# PSPS_AVNC_SRD_sensors-2020-10-23_FABRICA.net
KiCad netlist of a schematic drawn in EAGLE
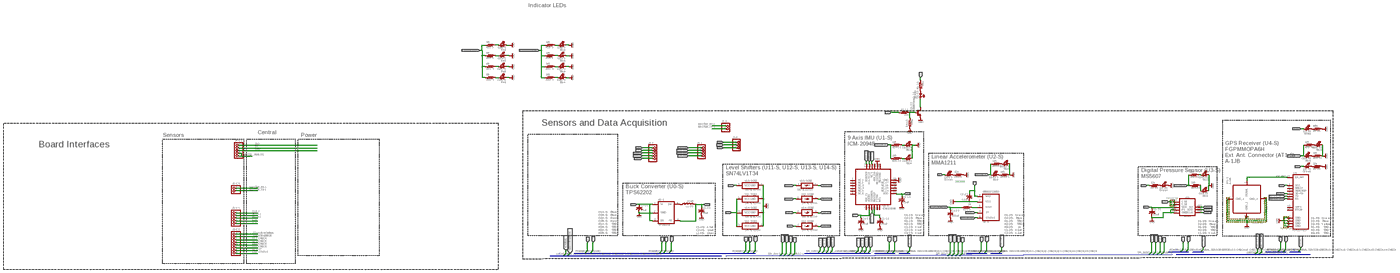
[diagram p0: schematic, sheet 1, overview]
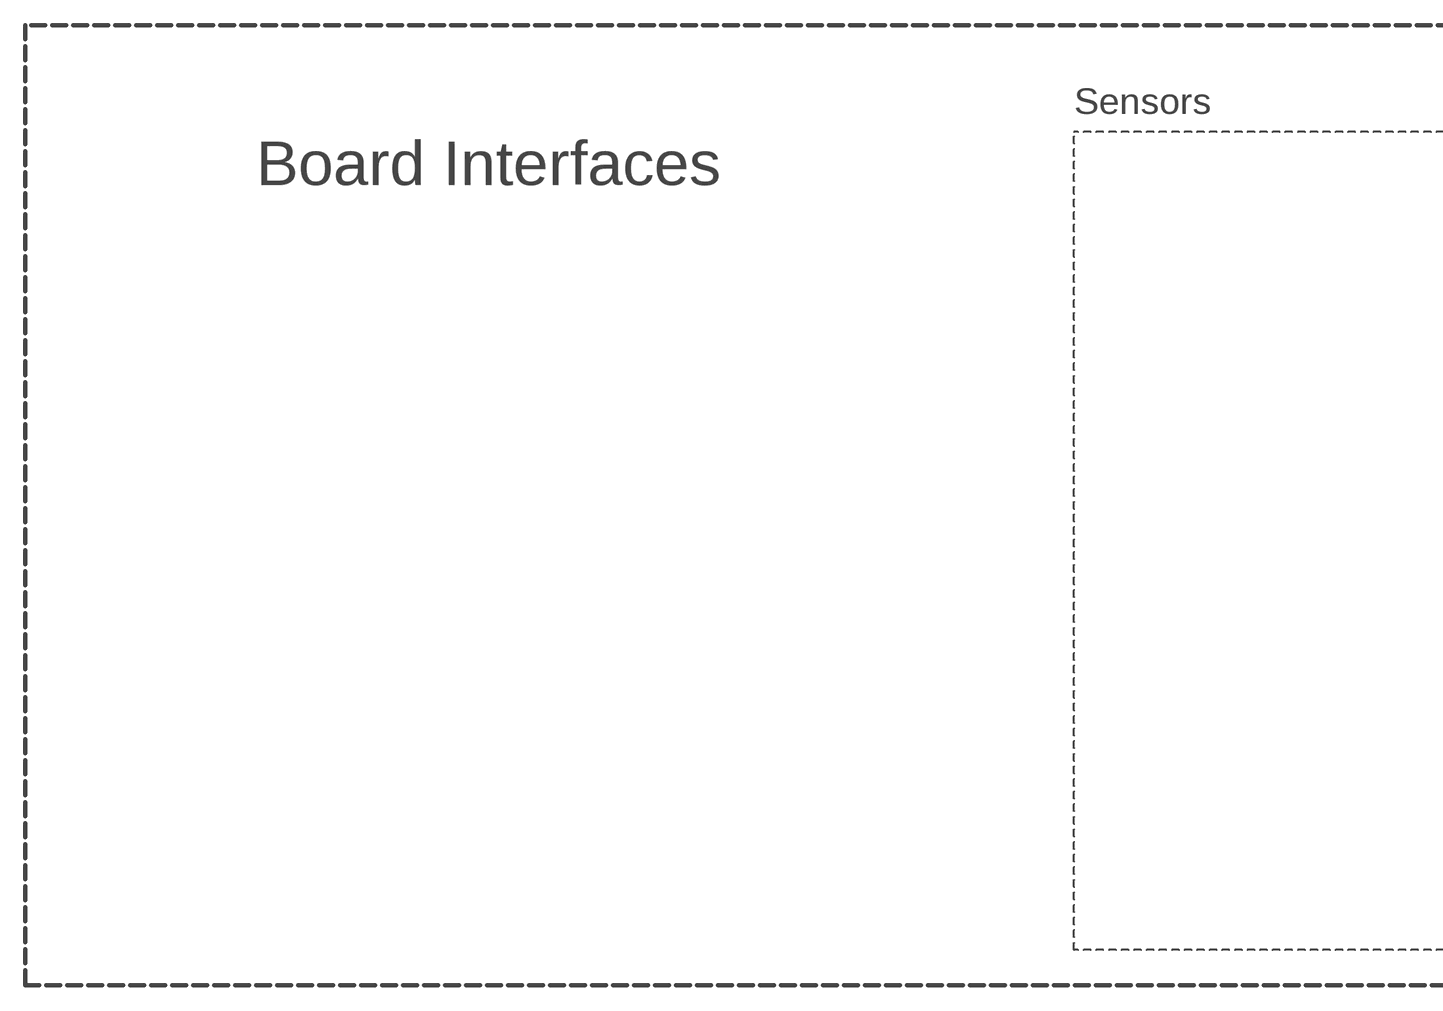
[diagram p1: schematic, sheet 1, part 1 of 4]
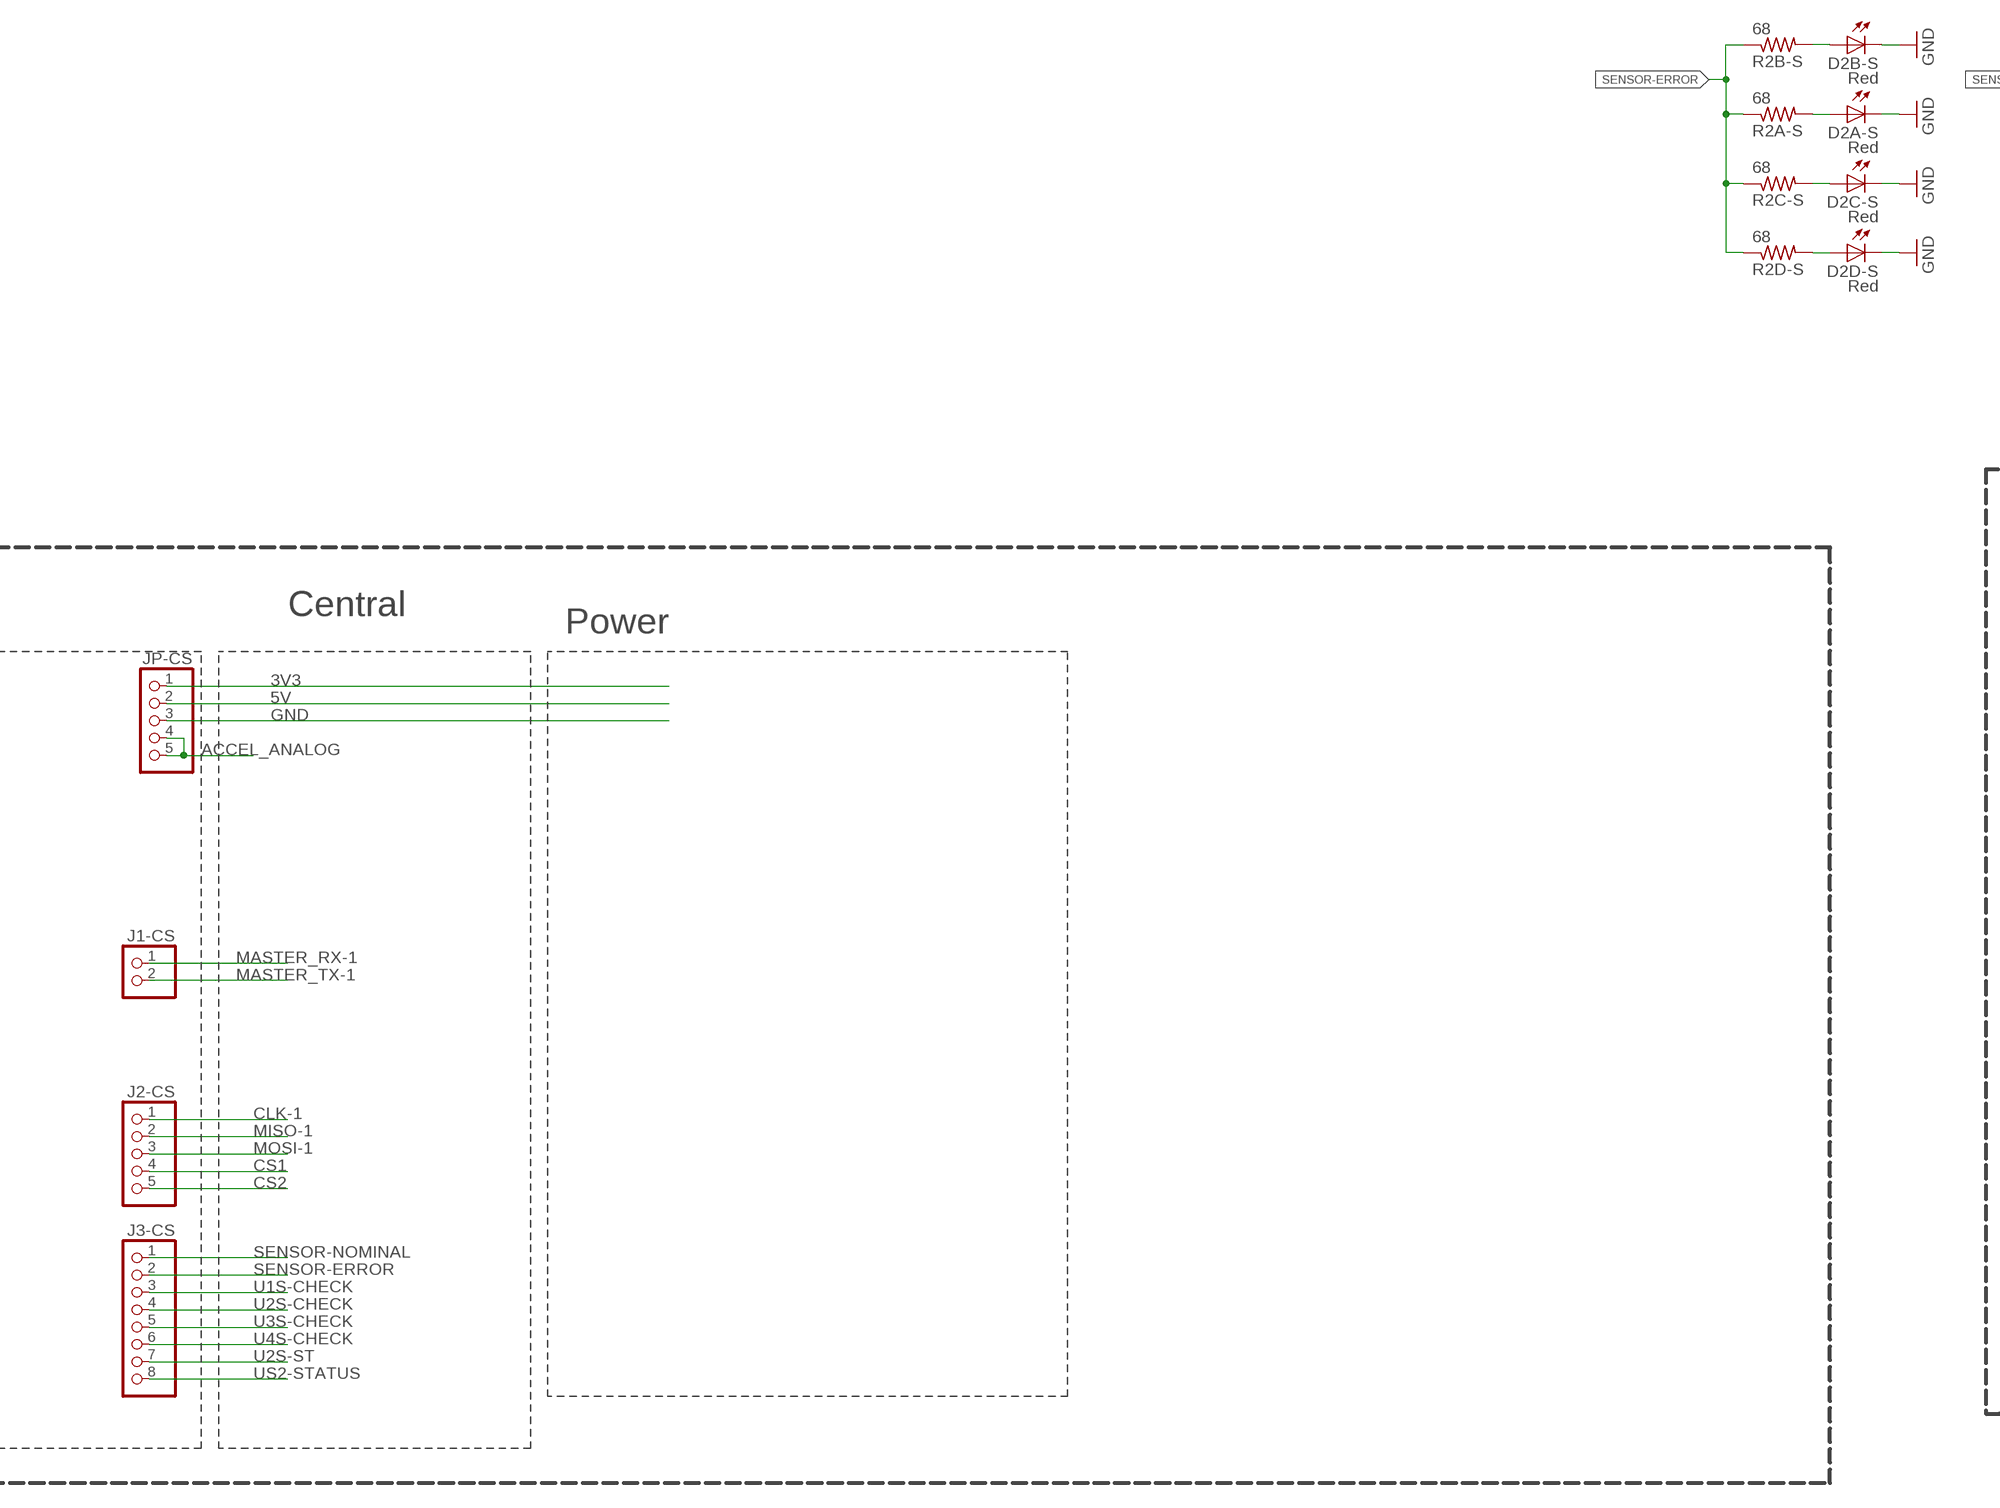
[diagram p2: schematic, sheet 1, part 2 of 4]
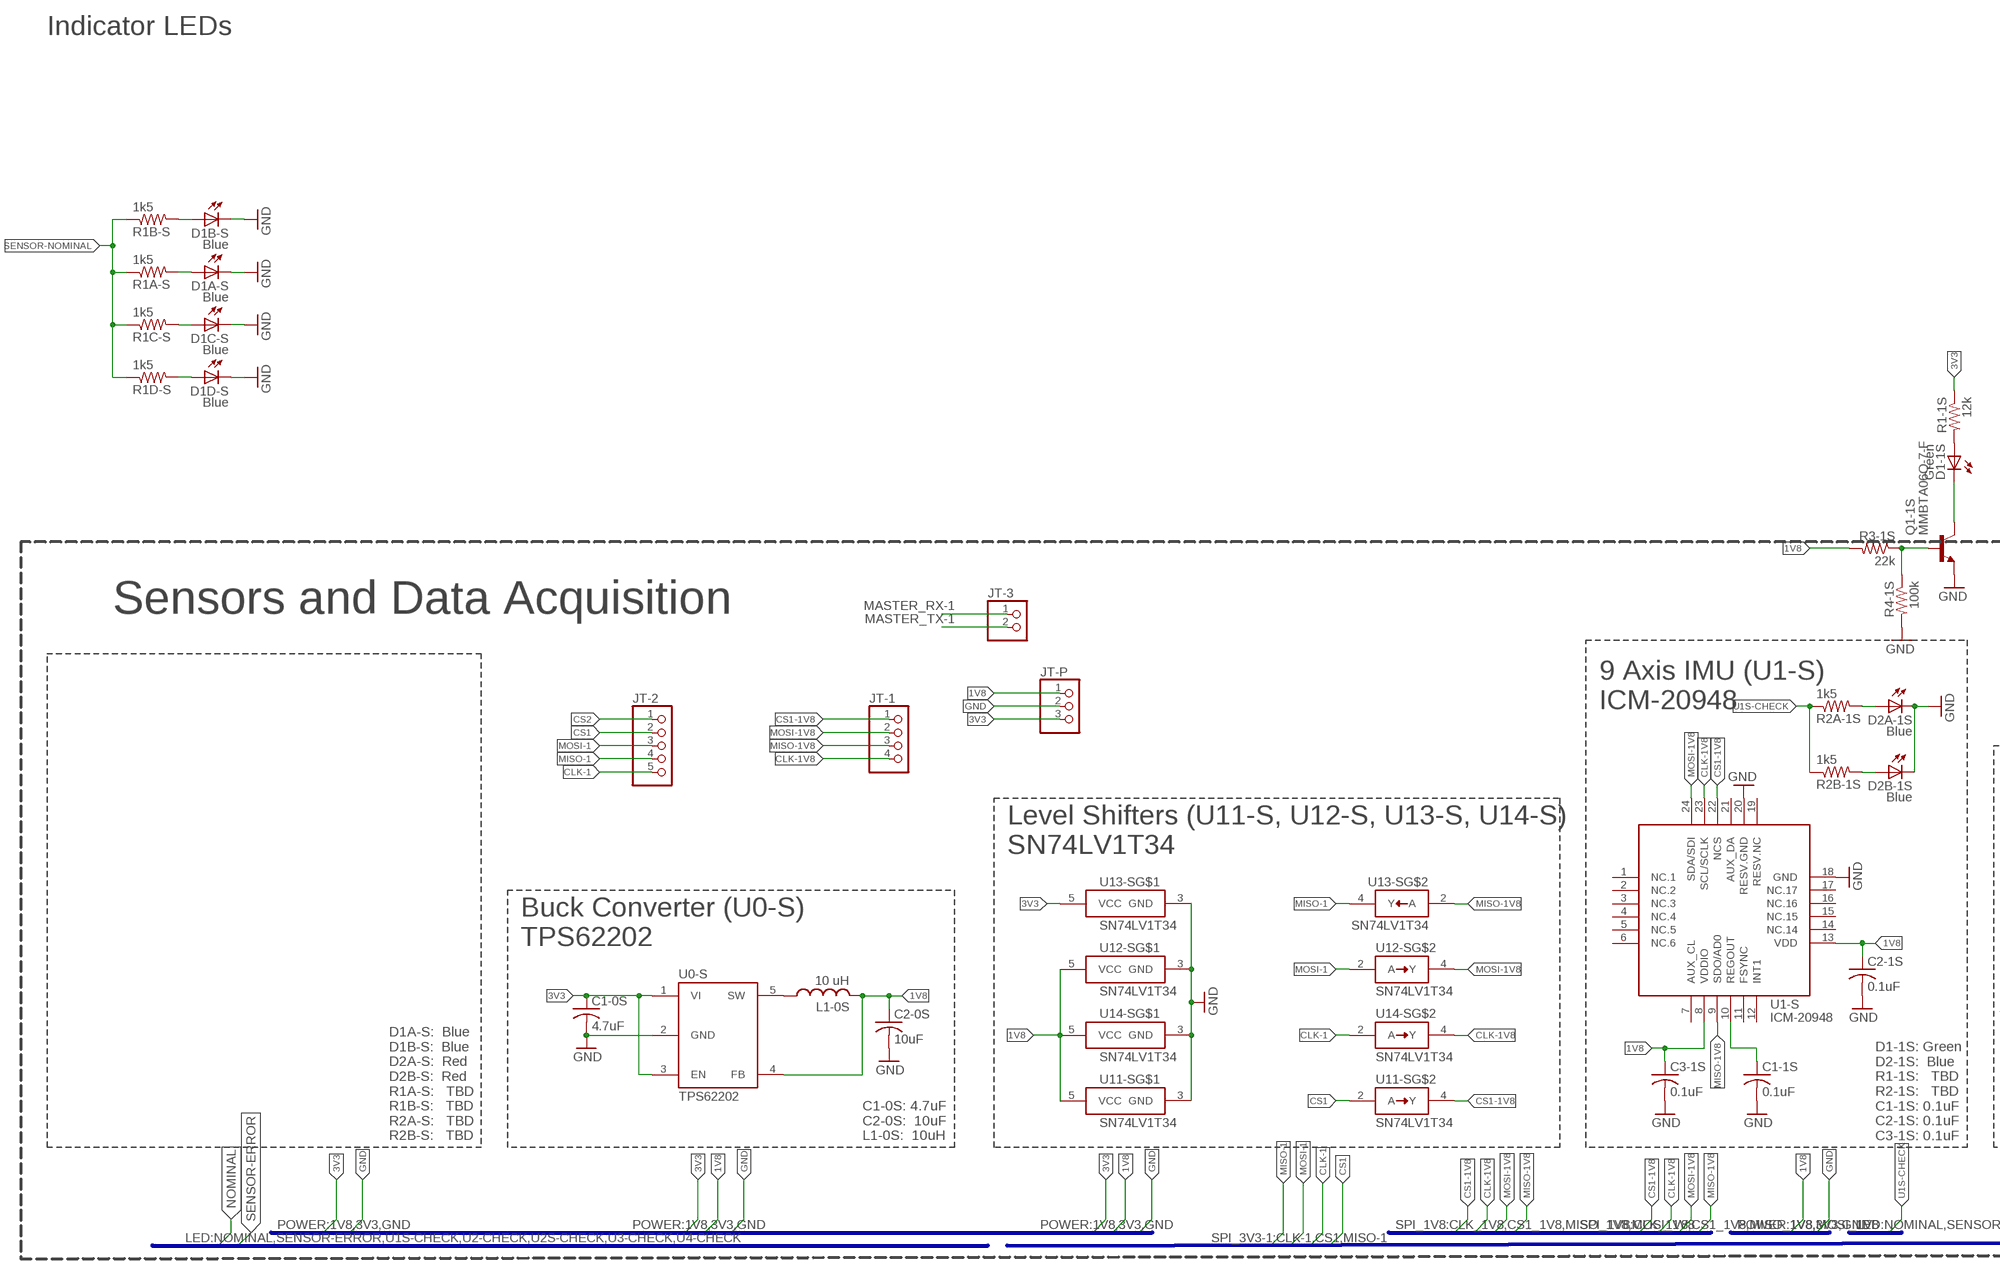
[diagram p3: schematic, sheet 1, part 3 of 4]
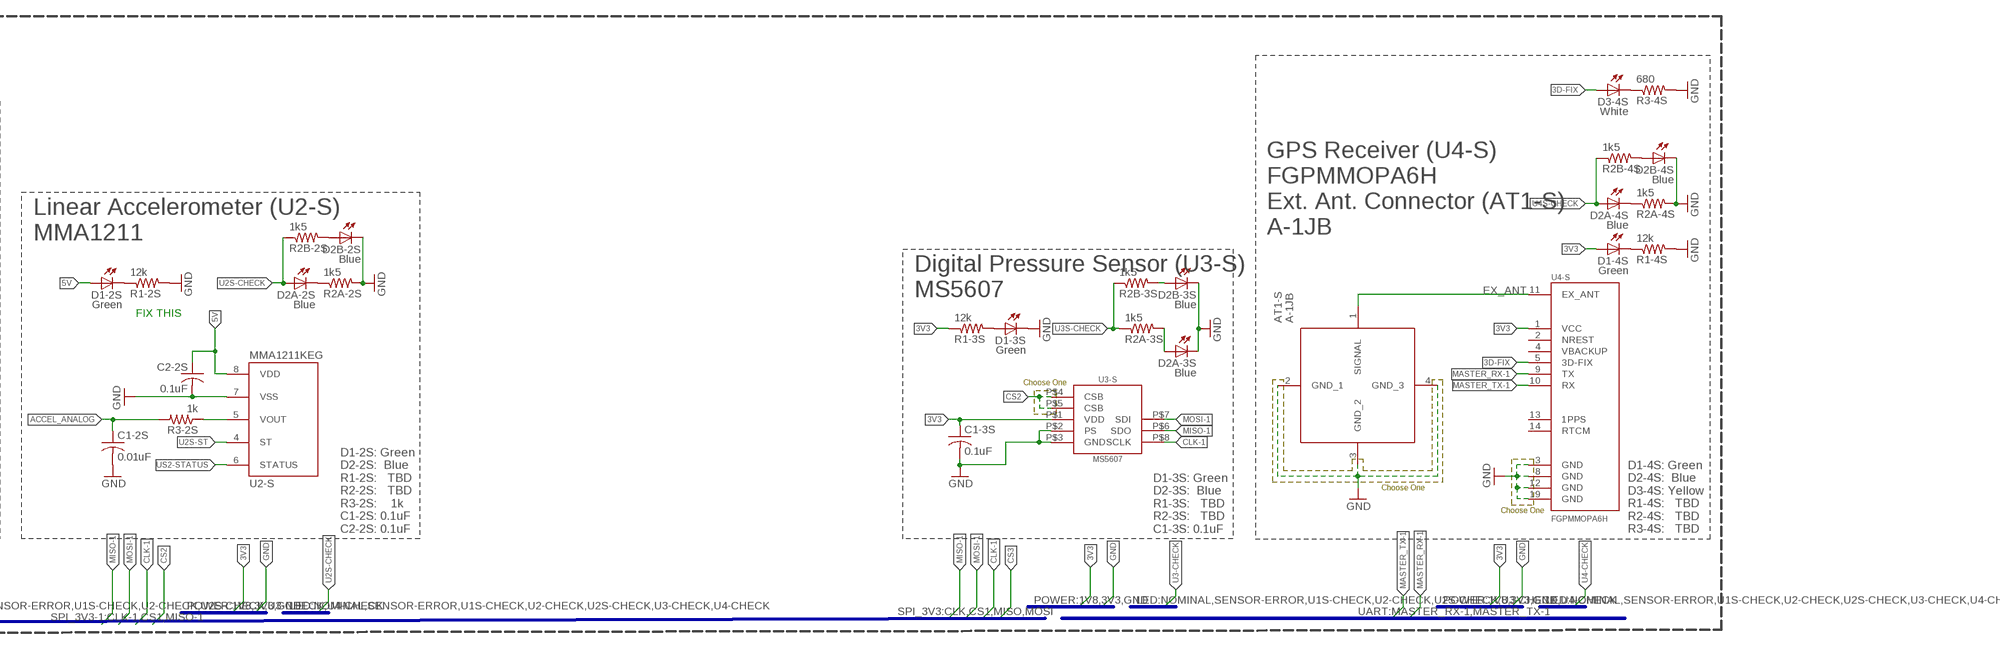
[diagram p4: schematic, sheet 1, part 4 of 4]

(export (version "E")
  (design (tool "Eeschema 10.0.6"))
  (components
    (comp (ref "AT1-S")
      (value "A-1JB")
      (footprint "eagle-import:A1JB")
      (fields (field (name "MOUSER_PART_NUMBER") "523-A-1JB"))
      (libsource (lib "eagle-import") (part "A-1JB"))
    )
    (comp (ref "C1-0S")
      (value "4.7uF")
      (footprint "eagle-import:C0805")
      (libsource (lib "eagle-import") (part "C-USC0805"))
    )
    (comp (ref "C1-1S")
      (value "0.1uF")
      (footprint "eagle-import:C0805")
      (libsource (lib "eagle-import") (part "C-USC0805"))
    )
    (comp (ref "C1-2S")
      (value "0.01uF")
      (footprint "eagle-import:C0805")
      (libsource (lib "eagle-import") (part "C-USC0805"))
    )
    (comp (ref "C1-3S")
      (value "0.1uF")
      (footprint "eagle-import:C0805")
      (libsource (lib "eagle-import") (part "C-USC0805"))
    )
    (comp (ref "C2-0S")
      (value "10uF")
      (footprint "eagle-import:C0805")
      (libsource (lib "eagle-import") (part "C-USC0805"))
    )
    (comp (ref "C2-1S")
      (value "0.1uF")
      (footprint "eagle-import:C0805")
      (libsource (lib "eagle-import") (part "C-USC0805"))
    )
    (comp (ref "C2-2S")
      (value "0.1uF")
      (footprint "eagle-import:C0805")
      (libsource (lib "eagle-import") (part "C-USC0805"))
    )
    (comp (ref "C3-1S")
      (value "0.1uF")
      (footprint "eagle-import:C0805")
      (libsource (lib "eagle-import") (part "C-USC0805"))
    )
    (comp (ref "D1-1S")
      (value "Green")
      (footprint "eagle-import:CHIPLED_0805")
      (libsource (lib "eagle-import") (part "LEDCHIPLED_0805"))
    )
    (comp (ref "D1-2S")
      (value "Green")
      (footprint "eagle-import:CHIPLED_0805")
      (libsource (lib "eagle-import") (part "LEDCHIPLED_0805"))
    )
    (comp (ref "D1-3S")
      (value "Green")
      (footprint "eagle-import:CHIPLED_0805")
      (libsource (lib "eagle-import") (part "LEDCHIPLED_0805"))
    )
    (comp (ref "D1-4S")
      (value "Green")
      (footprint "eagle-import:CHIPLED_0805")
      (libsource (lib "eagle-import") (part "LEDCHIPLED_0805"))
    )
    (comp (ref "D1A-S")
      (value "Blue")
      (footprint "eagle-import:CHIPLED_0805")
      (libsource (lib "eagle-import") (part "LEDCHIPLED_0805"))
    )
    (comp (ref "D1B-S")
      (value "Blue")
      (footprint "eagle-import:CHIPLED_0805")
      (libsource (lib "eagle-import") (part "LEDCHIPLED_0805"))
    )
    (comp (ref "D1C-S")
      (value "Blue")
      (footprint "eagle-import:CHIPLED_0805")
      (libsource (lib "eagle-import") (part "LEDCHIPLED_0805"))
    )
    (comp (ref "D1D-S")
      (value "Blue")
      (footprint "eagle-import:CHIPLED_0805")
      (libsource (lib "eagle-import") (part "LEDCHIPLED_0805"))
    )
    (comp (ref "D2A-1S")
      (value "Blue")
      (footprint "eagle-import:CHIPLED_0805")
      (libsource (lib "eagle-import") (part "LEDCHIPLED_0805"))
    )
    (comp (ref "D2A-2S")
      (value "Blue")
      (footprint "eagle-import:CHIPLED_0805")
      (libsource (lib "eagle-import") (part "LEDCHIPLED_0805"))
    )
    (comp (ref "D2A-3S")
      (value "Blue")
      (footprint "eagle-import:CHIPLED_0805")
      (libsource (lib "eagle-import") (part "LEDCHIPLED_0805"))
    )
    (comp (ref "D2A-4S")
      (value "Blue")
      (footprint "eagle-import:CHIPLED_0805")
      (libsource (lib "eagle-import") (part "LEDCHIPLED_0805"))
    )
    (comp (ref "D2A-S")
      (value "Red")
      (footprint "eagle-import:CHIPLED_0805")
      (libsource (lib "eagle-import") (part "LEDCHIPLED_0805"))
    )
    (comp (ref "D2B-1S")
      (value "Blue")
      (footprint "eagle-import:CHIPLED_0805")
      (libsource (lib "eagle-import") (part "LEDCHIPLED_0805"))
    )
    (comp (ref "D2B-2S")
      (value "Blue")
      (footprint "eagle-import:CHIPLED_0805")
      (libsource (lib "eagle-import") (part "LEDCHIPLED_0805"))
    )
    (comp (ref "D2B-3S")
      (value "Blue")
      (footprint "eagle-import:CHIPLED_0805")
      (libsource (lib "eagle-import") (part "LEDCHIPLED_0805"))
    )
    (comp (ref "D2B-4S")
      (value "Blue")
      (footprint "eagle-import:CHIPLED_0805")
      (libsource (lib "eagle-import") (part "LEDCHIPLED_0805"))
    )
    (comp (ref "D2B-S")
      (value "Red")
      (footprint "eagle-import:CHIPLED_0805")
      (libsource (lib "eagle-import") (part "LEDCHIPLED_0805"))
    )
    (comp (ref "D2C-S")
      (value "Red")
      (footprint "eagle-import:CHIPLED_0805")
      (libsource (lib "eagle-import") (part "LEDCHIPLED_0805"))
    )
    (comp (ref "D2D-S")
      (value "Red")
      (footprint "eagle-import:CHIPLED_0805")
      (libsource (lib "eagle-import") (part "LEDCHIPLED_0805"))
    )
    (comp (ref "D3-4S")
      (value "White")
      (footprint "eagle-import:CHIPLED_0805")
      (libsource (lib "eagle-import") (part "LEDCHIPLED_0805"))
    )
    (comp (ref "J1-CS")
      (value "PINHD-1X2")
      (footprint "eagle-import:1X02")
      (libsource (lib "eagle-import") (part "PINHD-1X2"))
    )
    (comp (ref "J2-CS")
      (value "PINHD-1X5")
      (footprint "eagle-import:1X05")
      (libsource (lib "eagle-import") (part "PINHD-1X5"))
    )
    (comp (ref "J3-CS")
      (value "PINHD-1X8")
      (footprint "eagle-import:1X08")
      (libsource (lib "eagle-import") (part "PINHD-1X8"))
    )
    (comp (ref "JP-CS")
      (value "PINHD-1X5")
      (footprint "eagle-import:1X05")
      (libsource (lib "eagle-import") (part "PINHD-1X5"))
    )
    (comp (ref "JT-1")
      (value "PINHD-1X4")
      (footprint "eagle-import:1X04")
      (libsource (lib "eagle-import") (part "PINHD-1X4"))
    )
    (comp (ref "JT-2")
      (value "PINHD-1X5")
      (footprint "eagle-import:1X05")
      (libsource (lib "eagle-import") (part "PINHD-1X5"))
    )
    (comp (ref "JT-3")
      (value "PINHD-1X2")
      (footprint "eagle-import:1X02")
      (libsource (lib "eagle-import") (part "PINHD-1X2"))
    )
    (comp (ref "JT-P")
      (value "PINHD-1X3")
      (footprint "eagle-import:1X03")
      (libsource (lib "eagle-import") (part "PINHD-1X3"))
    )
    (comp (ref "L1-0S")
      (value "10 uH")
      (footprint "eagle-import:L1812")
      (libsource (lib "eagle-import") (part "L-USL1812"))
    )
    (comp (ref "Q1-1S")
      (value "MMBTA06Q-7-F")
      (footprint "eagle-import:SOT23")
      (libsource (lib "eagle-import") (part "NPN_TRANSISTOR"))
    )
    (comp (ref "R1-1S")
      (value "12k")
      (footprint "eagle-import:R0805")
      (libsource (lib "eagle-import") (part "R-US_R0805"))
    )
    (comp (ref "R1-2S")
      (value "12k")
      (footprint "eagle-import:R0805")
      (libsource (lib "eagle-import") (part "R-US_R0805"))
    )
    (comp (ref "R1-3S")
      (value "12k")
      (footprint "eagle-import:R0805")
      (libsource (lib "eagle-import") (part "R-US_R0805"))
    )
    (comp (ref "R1-4S")
      (value "12k")
      (footprint "eagle-import:R0805")
      (libsource (lib "eagle-import") (part "R-US_R0805"))
    )
    (comp (ref "R1A-S")
      (value "1k5")
      (footprint "eagle-import:R0805")
      (libsource (lib "eagle-import") (part "R-US_R0805"))
    )
    (comp (ref "R1B-S")
      (value "1k5")
      (footprint "eagle-import:R0805")
      (libsource (lib "eagle-import") (part "R-US_R0805"))
    )
    (comp (ref "R1C-S")
      (value "1k5")
      (footprint "eagle-import:R0805")
      (libsource (lib "eagle-import") (part "R-US_R0805"))
    )
    (comp (ref "R1D-S")
      (value "1k5")
      (footprint "eagle-import:R0805")
      (libsource (lib "eagle-import") (part "R-US_R0805"))
    )
    (comp (ref "R2A-1S")
      (value "1k5")
      (footprint "eagle-import:R0805")
      (libsource (lib "eagle-import") (part "R-US_R0805"))
    )
    (comp (ref "R2A-2S")
      (value "1k5")
      (footprint "eagle-import:R0805")
      (libsource (lib "eagle-import") (part "R-US_R0805"))
    )
    (comp (ref "R2A-3S")
      (value "1k5")
      (footprint "eagle-import:R0805")
      (libsource (lib "eagle-import") (part "R-US_R0805"))
    )
    (comp (ref "R2A-4S")
      (value "1k5")
      (footprint "eagle-import:R0805")
      (libsource (lib "eagle-import") (part "R-US_R0805"))
    )
    (comp (ref "R2A-S")
      (value "68")
      (footprint "eagle-import:R0805")
      (libsource (lib "eagle-import") (part "R-US_R0805"))
    )
    (comp (ref "R2B-1S")
      (value "1k5")
      (footprint "eagle-import:R0805")
      (libsource (lib "eagle-import") (part "R-US_R0805"))
    )
    (comp (ref "R2B-2S")
      (value "1k5")
      (footprint "eagle-import:R0805")
      (libsource (lib "eagle-import") (part "R-US_R0805"))
    )
    (comp (ref "R2B-3S")
      (value "1k5")
      (footprint "eagle-import:R0805")
      (libsource (lib "eagle-import") (part "R-US_R0805"))
    )
    (comp (ref "R2B-4S")
      (value "1k5")
      (footprint "eagle-import:R0805")
      (libsource (lib "eagle-import") (part "R-US_R0805"))
    )
    (comp (ref "R2B-S")
      (value "68")
      (footprint "eagle-import:R0805")
      (libsource (lib "eagle-import") (part "R-US_R0805"))
    )
    (comp (ref "R2C-S")
      (value "68")
      (footprint "eagle-import:R0805")
      (libsource (lib "eagle-import") (part "R-US_R0805"))
    )
    (comp (ref "R2D-S")
      (value "68")
      (footprint "eagle-import:R0805")
      (libsource (lib "eagle-import") (part "R-US_R0805"))
    )
    (comp (ref "R3-1S")
      (value "22k")
      (footprint "eagle-import:R0805")
      (libsource (lib "eagle-import") (part "R-US_R0805"))
    )
    (comp (ref "R3-2S")
      (value "1k")
      (footprint "eagle-import:R0805")
      (libsource (lib "eagle-import") (part "R-US_R0805"))
    )
    (comp (ref "R3-4S")
      (value "680")
      (footprint "eagle-import:R0805")
      (libsource (lib "eagle-import") (part "R-US_R0805"))
    )
    (comp (ref "R4-1S")
      (value "100k")
      (footprint "eagle-import:R0805")
      (libsource (lib "eagle-import") (part "R-US_R0805"))
    )
    (comp (ref "U0-S")
      (value "TPS62202")
      (footprint "eagle-import:SOT95P280X145-5")
      (libsource (lib "eagle-import") (part "TPS62202"))
    )
    (comp (ref "U1-S")
      (value "ICM-20948")
      (footprint "eagle-import:QFN40P300X300X105-25T159X175")
      (libsource (lib "eagle-import") (part "ICM-20948"))
    )
    (comp (ref "U2-S")
      (value "MMA1211KEG")
      (footprint "eagle-import:SOIC127P1041X355-16N")
      (libsource (lib "eagle-import") (part "MMA1211KEG"))
    )
    (comp (ref "U3-S")
      (value "MS5607")
      (footprint "eagle-import:MS5607")
      (libsource (lib "eagle-import") (part "MS5607"))
    )
    (comp (ref "U4-S")
      (value "FGPMMOPA6H")
      (footprint "eagle-import:SOIC127P1800X470-20N")
      (libsource (lib "eagle-import") (part "FGPMMOPA6H"))
    )
    (comp (ref "U11-S")
      (value "SN74LV1T34")
      (footprint "eagle-import:SOT65P210X110-5")
      (libsource (lib "eagle-import") (part "SN74LV1T34"))
    )
    (comp (ref "U12-S")
      (value "SN74LV1T34")
      (footprint "eagle-import:SOT65P210X110-5")
      (libsource (lib "eagle-import") (part "SN74LV1T34"))
    )
    (comp (ref "U13-S")
      (value "SN74LV1T34")
      (footprint "eagle-import:SOT65P210X110-5")
      (libsource (lib "eagle-import") (part "SN74LV1T34"))
    )
    (comp (ref "U14-S")
      (value "SN74LV1T34")
      (footprint "eagle-import:SOT65P210X110-5")
      (libsource (lib "eagle-import") (part "SN74LV1T34"))
    )
  )
  (nets
    (net (code "13") (name "/EX_ANT") (class "Default")
      (node (ref "AT1-S") (pin "1") (pinfunction "SIGNAL_1") (pintype "bidirectional"))
      (node (ref "U4-S") (pin "11") (pinfunction "EX_ANT_11") (pintype "bidirectional"))
    )
    (net (code "20") (name "1V8") (class "Default")
      (node (ref "C2-0S") (pin "1") (pinfunction "1_1") (pintype "passive"))
      (node (ref "C2-1S") (pin "1") (pinfunction "1_1") (pintype "passive"))
      (node (ref "C3-1S") (pin "1") (pinfunction "1_1") (pintype "passive"))
      (node (ref "JT-P") (pin "1") (pinfunction "1_1") (pintype "passive"))
      (node (ref "L1-0S") (pin "2") (pinfunction "2_2") (pintype "passive"))
      (node (ref "R3-1S") (pin "2") (pinfunction "2_2") (pintype "passive"))
      (node (ref "U0-S") (pin "4") (pinfunction "FB_4") (pintype "bidirectional"))
      (node (ref "U1-S") (pin "13") (pinfunction "VDD_13") (pintype "bidirectional"))
      (node (ref "U1-S") (pin "8") (pinfunction "VDDIO_8") (pintype "bidirectional"))
      (node (ref "U11-S") (pin "5") (pinfunction "VCC_5") (pintype "bidirectional"))
      (node (ref "U12-S") (pin "5") (pinfunction "VCC_5") (pintype "bidirectional"))
      (node (ref "U14-S") (pin "5") (pinfunction "VCC_5") (pintype "bidirectional"))
    )
    (net (code "21") (name "3D-FIX") (class "Default")
      (node (ref "D3-4S") (pin "A") (pinfunction "A_A") (pintype "passive"))
      (node (ref "U4-S") (pin "5") (pinfunction "3D-FIX_5") (pintype "bidirectional"))
    )
    (net (code "22") (name "3V3") (class "Default")
      (node (ref "C1-0S") (pin "1") (pinfunction "1_1") (pintype "passive"))
      (node (ref "C1-3S") (pin "1") (pinfunction "1_1") (pintype "passive"))
      (node (ref "D1-4S") (pin "A") (pinfunction "A_A") (pintype "passive"))
      (node (ref "JP-CS") (pin "1") (pinfunction "1_1") (pintype "passive"))
      (node (ref "JT-P") (pin "3") (pinfunction "3_3") (pintype "passive"))
      (node (ref "R1-1S") (pin "1") (pinfunction "1_1") (pintype "passive"))
      (node (ref "R1-3S") (pin "1") (pinfunction "1_1") (pintype "passive"))
      (node (ref "U0-S") (pin "1") (pinfunction "VI_1") (pintype "bidirectional"))
      (node (ref "U0-S") (pin "3") (pinfunction "EN_3") (pintype "bidirectional"))
      (node (ref "U13-S") (pin "5") (pinfunction "VCC_5") (pintype "bidirectional"))
      (node (ref "U3-S") (pin "P$1") (pinfunction "VDD_P$1") (pintype "bidirectional"))
      (node (ref "U4-S") (pin "1") (pinfunction "VCC_1") (pintype "bidirectional"))
    )
    (net (code "23") (name "5V") (class "Default")
      (node (ref "C2-2S") (pin "1") (pinfunction "1_1") (pintype "passive"))
      (node (ref "D1-2S") (pin "A") (pinfunction "A_A") (pintype "passive"))
      (node (ref "JP-CS") (pin "2") (pinfunction "2_2") (pintype "passive"))
      (node (ref "U2-S") (pin "8") (pinfunction "VDD_8") (pintype "bidirectional"))
    )
    (net (code "24") (name "ACCEL_ANALOG") (class "Default")
      (node (ref "C1-2S") (pin "1") (pinfunction "1_1") (pintype "passive"))
      (node (ref "JP-CS") (pin "4") (pinfunction "4_4") (pintype "passive"))
      (node (ref "JP-CS") (pin "5") (pinfunction "5_5") (pintype "passive"))
      (node (ref "R3-2S") (pin "2") (pinfunction "2_2") (pintype "passive"))
    )
    (net (code "25") (name "CLK-1") (class "Default")
      (node (ref "J2-CS") (pin "1") (pinfunction "1_1") (pintype "passive"))
      (node (ref "JT-2") (pin "5") (pinfunction "5_5") (pintype "passive"))
      (node (ref "U14-S") (pin "2") (pinfunction "A_2") (pintype "bidirectional"))
      (node (ref "U3-S") (pin "P$8") (pinfunction "SCLK_P$8") (pintype "bidirectional"))
    )
    (net (code "26") (name "CLK-1V8") (class "Default")
      (node (ref "JT-1") (pin "4") (pinfunction "4_4") (pintype "passive"))
      (node (ref "U1-S") (pin "23") (pinfunction "SCL/SCLK_23") (pintype "bidirectional"))
      (node (ref "U14-S") (pin "4") (pinfunction "Y_4") (pintype "bidirectional"))
    )
    (net (code "27") (name "CS1") (class "Default")
      (node (ref "J2-CS") (pin "4") (pinfunction "4_4") (pintype "passive"))
      (node (ref "JT-2") (pin "2") (pinfunction "2_2") (pintype "passive"))
      (node (ref "U11-S") (pin "2") (pinfunction "A_2") (pintype "bidirectional"))
    )
    (net (code "28") (name "CS1-1V8") (class "Default")
      (node (ref "JT-1") (pin "1") (pinfunction "1_1") (pintype "passive"))
      (node (ref "U1-S") (pin "22") (pinfunction "NCS_22") (pintype "bidirectional"))
      (node (ref "U11-S") (pin "4") (pinfunction "Y_4") (pintype "bidirectional"))
    )
    (net (code "29") (name "CS2") (class "Default")
      (node (ref "J2-CS") (pin "5") (pinfunction "5_5") (pintype "passive"))
      (node (ref "JT-2") (pin "1") (pinfunction "1_1") (pintype "passive"))
      (node (ref "U3-S") (pin "P$4") (pinfunction "CSB_P$4") (pintype "bidirectional"))
      (node (ref "U3-S") (pin "P$5") (pinfunction "CSB_P$5") (pintype "bidirectional"))
    )
    (net (code "31") (name "GND") (class "Default")
      (node (ref "AT1-S") (pin "2") (pinfunction "GND_1_2") (pintype "bidirectional"))
      (node (ref "AT1-S") (pin "3") (pinfunction "GND_2_3") (pintype "bidirectional"))
      (node (ref "AT1-S") (pin "4") (pinfunction "GND_3_4") (pintype "bidirectional"))
      (node (ref "C1-0S") (pin "2") (pinfunction "2_2") (pintype "passive"))
      (node (ref "C1-1S") (pin "2") (pinfunction "2_2") (pintype "passive"))
      (node (ref "C1-2S") (pin "2") (pinfunction "2_2") (pintype "passive"))
      (node (ref "C1-3S") (pin "2") (pinfunction "2_2") (pintype "passive"))
      (node (ref "C2-0S") (pin "2") (pinfunction "2_2") (pintype "passive"))
      (node (ref "C2-1S") (pin "2") (pinfunction "2_2") (pintype "passive"))
      (node (ref "C2-2S") (pin "2") (pinfunction "2_2") (pintype "passive"))
      (node (ref "C3-1S") (pin "2") (pinfunction "2_2") (pintype "passive"))
      (node (ref "D1-3S") (pin "C") (pinfunction "C_C") (pintype "passive"))
      (node (ref "D1A-S") (pin "C") (pinfunction "C_C") (pintype "passive"))
      (node (ref "D1B-S") (pin "C") (pinfunction "C_C") (pintype "passive"))
      (node (ref "D1C-S") (pin "C") (pinfunction "C_C") (pintype "passive"))
      (node (ref "D1D-S") (pin "C") (pinfunction "C_C") (pintype "passive"))
      (node (ref "D2A-1S") (pin "C") (pinfunction "C_C") (pintype "passive"))
      (node (ref "D2A-3S") (pin "C") (pinfunction "C_C") (pintype "passive"))
      (node (ref "D2A-S") (pin "C") (pinfunction "C_C") (pintype "passive"))
      (node (ref "D2B-1S") (pin "C") (pinfunction "C_C") (pintype "passive"))
      (node (ref "D2B-2S") (pin "C") (pinfunction "C_C") (pintype "passive"))
      (node (ref "D2B-3S") (pin "C") (pinfunction "C_C") (pintype "passive"))
      (node (ref "D2B-4S") (pin "C") (pinfunction "C_C") (pintype "passive"))
      (node (ref "D2B-S") (pin "C") (pinfunction "C_C") (pintype "passive"))
      (node (ref "D2C-S") (pin "C") (pinfunction "C_C") (pintype "passive"))
      (node (ref "D2D-S") (pin "C") (pinfunction "C_C") (pintype "passive"))
      (node (ref "JP-CS") (pin "3") (pinfunction "3_3") (pintype "passive"))
      (node (ref "JT-P") (pin "2") (pinfunction "2_2") (pintype "passive"))
      (node (ref "Q1-1S") (pin "3") (pinfunction "E_3") (pintype "passive"))
      (node (ref "R1-2S") (pin "2") (pinfunction "2_2") (pintype "passive"))
      (node (ref "R1-4S") (pin "2") (pinfunction "2_2") (pintype "passive"))
      (node (ref "R2A-2S") (pin "2") (pinfunction "2_2") (pintype "passive"))
      (node (ref "R2A-4S") (pin "2") (pinfunction "2_2") (pintype "passive"))
      (node (ref "R3-4S") (pin "2") (pinfunction "2_2") (pintype "passive"))
      (node (ref "R4-1S") (pin "2") (pinfunction "2_2") (pintype "passive"))
      (node (ref "U0-S") (pin "2") (pinfunction "GND_2") (pintype "bidirectional"))
      (node (ref "U1-S") (pin "18") (pinfunction "GND_18") (pintype "bidirectional"))
      (node (ref "U1-S") (pin "20") (pinfunction "RESV.GND_20") (pintype "bidirectional"))
      (node (ref "U11-S") (pin "3") (pinfunction "GND_3") (pintype "bidirectional"))
      (node (ref "U12-S") (pin "3") (pinfunction "GND_3") (pintype "bidirectional"))
      (node (ref "U13-S") (pin "3") (pinfunction "GND_3") (pintype "bidirectional"))
      (node (ref "U14-S") (pin "3") (pinfunction "GND_3") (pintype "bidirectional"))
      (node (ref "U2-S") (pin "7") (pinfunction "VSS_7") (pintype "bidirectional"))
      (node (ref "U3-S") (pin "P$2") (pinfunction "PS_P$2") (pintype "bidirectional"))
      (node (ref "U3-S") (pin "P$3") (pinfunction "GND_P$3") (pintype "bidirectional"))
      (node (ref "U4-S") (pin "12") (pinfunction "GND_12") (pintype "bidirectional"))
      (node (ref "U4-S") (pin "19") (pinfunction "GND_19") (pintype "bidirectional"))
      (node (ref "U4-S") (pin "3") (pinfunction "GND_3") (pintype "bidirectional"))
      (node (ref "U4-S") (pin "8") (pinfunction "GND_8") (pintype "bidirectional"))
    )
    (net (code "32") (name "MASTER_RX-1") (class "Default")
      (node (ref "J1-CS") (pin "1") (pinfunction "1_1") (pintype "passive"))
      (node (ref "JT-3") (pin "1") (pinfunction "1_1") (pintype "passive"))
      (node (ref "U4-S") (pin "9") (pinfunction "TX_9") (pintype "bidirectional"))
    )
    (net (code "33") (name "MASTER_TX-1") (class "Default")
      (node (ref "J1-CS") (pin "2") (pinfunction "2_2") (pintype "passive"))
      (node (ref "JT-3") (pin "2") (pinfunction "2_2") (pintype "passive"))
      (node (ref "U4-S") (pin "10") (pinfunction "RX_10") (pintype "bidirectional"))
    )
    (net (code "34") (name "MISO-1") (class "Default")
      (node (ref "J2-CS") (pin "2") (pinfunction "2_2") (pintype "passive"))
      (node (ref "JT-2") (pin "4") (pinfunction "4_4") (pintype "passive"))
      (node (ref "U13-S") (pin "4") (pinfunction "Y_4") (pintype "bidirectional"))
      (node (ref "U3-S") (pin "P$6") (pinfunction "SDO_P$6") (pintype "bidirectional"))
    )
    (net (code "35") (name "MISO-1V8") (class "Default")
      (node (ref "JT-1") (pin "3") (pinfunction "3_3") (pintype "passive"))
      (node (ref "U1-S") (pin "9") (pinfunction "SDO/AD0_9") (pintype "bidirectional"))
      (node (ref "U13-S") (pin "2") (pinfunction "A_2") (pintype "bidirectional"))
    )
    (net (code "36") (name "MOSI-1") (class "Default")
      (node (ref "J2-CS") (pin "3") (pinfunction "3_3") (pintype "passive"))
      (node (ref "JT-2") (pin "3") (pinfunction "3_3") (pintype "passive"))
      (node (ref "U12-S") (pin "2") (pinfunction "A_2") (pintype "bidirectional"))
      (node (ref "U3-S") (pin "P$7") (pinfunction "SDI_P$7") (pintype "bidirectional"))
    )
    (net (code "37") (name "MOSI-1V8") (class "Default")
      (node (ref "JT-1") (pin "2") (pinfunction "2_2") (pintype "passive"))
      (node (ref "U1-S") (pin "24") (pinfunction "SDA/SDI_24") (pintype "bidirectional"))
      (node (ref "U12-S") (pin "4") (pinfunction "Y_4") (pintype "bidirectional"))
    )
    (net (code "39") (name "Net-(D1-1S-PadA)") (class "Default")
      (node (ref "D1-1S") (pin "A") (pinfunction "A_A") (pintype "passive"))
      (node (ref "R1-1S") (pin "2") (pinfunction "2_2") (pintype "passive"))
    )
    (net (code "40") (name "Net-(D1-2S-PadC)") (class "Default")
      (node (ref "D1-2S") (pin "C") (pinfunction "C_C") (pintype "passive"))
      (node (ref "R1-2S") (pin "1") (pinfunction "1_1") (pintype "passive"))
    )
    (net (code "41") (name "Net-(D1-3S-PadA)") (class "Default")
      (node (ref "D1-3S") (pin "A") (pinfunction "A_A") (pintype "passive"))
      (node (ref "R1-3S") (pin "2") (pinfunction "2_2") (pintype "passive"))
    )
    (net (code "42") (name "Net-(D1-4S-PadC)") (class "Default")
      (node (ref "D1-4S") (pin "C") (pinfunction "C_C") (pintype "passive"))
      (node (ref "R1-4S") (pin "1") (pinfunction "1_1") (pintype "passive"))
    )
    (net (code "43") (name "Net-(D1A-S-PadA)") (class "Default")
      (node (ref "D1A-S") (pin "A") (pinfunction "A_A") (pintype "passive"))
      (node (ref "R1A-S") (pin "2") (pinfunction "2_2") (pintype "passive"))
    )
    (net (code "44") (name "Net-(D1B-S-PadA)") (class "Default")
      (node (ref "D1B-S") (pin "A") (pinfunction "A_A") (pintype "passive"))
      (node (ref "R1B-S") (pin "2") (pinfunction "2_2") (pintype "passive"))
    )
    (net (code "45") (name "Net-(D1C-S-PadA)") (class "Default")
      (node (ref "D1C-S") (pin "A") (pinfunction "A_A") (pintype "passive"))
      (node (ref "R1C-S") (pin "2") (pinfunction "2_2") (pintype "passive"))
    )
    (net (code "46") (name "Net-(D1D-S-PadA)") (class "Default")
      (node (ref "D1D-S") (pin "A") (pinfunction "A_A") (pintype "passive"))
      (node (ref "R1D-S") (pin "2") (pinfunction "2_2") (pintype "passive"))
    )
    (net (code "47") (name "Net-(D2A-1S-PadA)") (class "Default")
      (node (ref "D2A-1S") (pin "A") (pinfunction "A_A") (pintype "passive"))
      (node (ref "R2A-1S") (pin "2") (pinfunction "2_2") (pintype "passive"))
    )
    (net (code "48") (name "Net-(D2A-2S-PadC)") (class "Default")
      (node (ref "D2A-2S") (pin "C") (pinfunction "C_C") (pintype "passive"))
      (node (ref "R2A-2S") (pin "1") (pinfunction "1_1") (pintype "passive"))
    )
    (net (code "49") (name "Net-(D2A-3S-PadA)") (class "Default")
      (node (ref "D2A-3S") (pin "A") (pinfunction "A_A") (pintype "passive"))
      (node (ref "R2A-3S") (pin "2") (pinfunction "2_2") (pintype "passive"))
    )
    (net (code "50") (name "Net-(D2A-4S-PadC)") (class "Default")
      (node (ref "D2A-4S") (pin "C") (pinfunction "C_C") (pintype "passive"))
      (node (ref "R2A-4S") (pin "1") (pinfunction "1_1") (pintype "passive"))
    )
    (net (code "51") (name "Net-(D2A-S-PadA)") (class "Default")
      (node (ref "D2A-S") (pin "A") (pinfunction "A_A") (pintype "passive"))
      (node (ref "R2A-S") (pin "2") (pinfunction "2_2") (pintype "passive"))
    )
    (net (code "52") (name "Net-(D2B-1S-PadA)") (class "Default")
      (node (ref "D2B-1S") (pin "A") (pinfunction "A_A") (pintype "passive"))
      (node (ref "R2B-1S") (pin "2") (pinfunction "2_2") (pintype "passive"))
    )
    (net (code "53") (name "Net-(D2B-2S-PadA)") (class "Default")
      (node (ref "D2B-2S") (pin "A") (pinfunction "A_A") (pintype "passive"))
      (node (ref "R2B-2S") (pin "2") (pinfunction "2_2") (pintype "passive"))
    )
    (net (code "54") (name "Net-(D2B-3S-PadA)") (class "Default")
      (node (ref "D2B-3S") (pin "A") (pinfunction "A_A") (pintype "passive"))
      (node (ref "R2B-3S") (pin "2") (pinfunction "2_2") (pintype "passive"))
    )
    (net (code "55") (name "Net-(D2B-4S-PadA)") (class "Default")
      (node (ref "D2B-4S") (pin "A") (pinfunction "A_A") (pintype "passive"))
      (node (ref "R2B-4S") (pin "2") (pinfunction "2_2") (pintype "passive"))
    )
    (net (code "56") (name "Net-(D2B-S-PadA)") (class "Default")
      (node (ref "D2B-S") (pin "A") (pinfunction "A_A") (pintype "passive"))
      (node (ref "R2B-S") (pin "2") (pinfunction "2_2") (pintype "passive"))
    )
    (net (code "57") (name "Net-(D2C-S-PadA)") (class "Default")
      (node (ref "D2C-S") (pin "A") (pinfunction "A_A") (pintype "passive"))
      (node (ref "R2C-S") (pin "2") (pinfunction "2_2") (pintype "passive"))
    )
    (net (code "58") (name "Net-(D2D-S-PadA)") (class "Default")
      (node (ref "D2D-S") (pin "A") (pinfunction "A_A") (pintype "passive"))
      (node (ref "R2D-S") (pin "2") (pinfunction "2_2") (pintype "passive"))
    )
    (net (code "59") (name "Net-(D3-4S-PadC)") (class "Default")
      (node (ref "D3-4S") (pin "C") (pinfunction "C_C") (pintype "passive"))
      (node (ref "R3-4S") (pin "1") (pinfunction "1_1") (pintype "passive"))
    )
    (net (code "60") (name "Net-(Q1-1S-B)") (class "Default")
      (node (ref "Q1-1S") (pin "1") (pinfunction "B_1") (pintype "passive"))
      (node (ref "R3-1S") (pin "1") (pinfunction "1_1") (pintype "passive"))
      (node (ref "R4-1S") (pin "1") (pinfunction "1_1") (pintype "passive"))
    )
    (net (code "61") (name "Net-(Q1-1S-C)") (class "Default")
      (node (ref "D1-1S") (pin "C") (pinfunction "C_C") (pintype "passive"))
      (node (ref "Q1-1S") (pin "2") (pinfunction "C_2") (pintype "passive"))
    )
    (net (code "62") (name "Net-(U0-S-SW)") (class "Default")
      (node (ref "L1-0S") (pin "1") (pinfunction "1_1") (pintype "passive"))
      (node (ref "U0-S") (pin "5") (pinfunction "SW_5") (pintype "bidirectional"))
    )
    (net (code "63") (name "Net-(U1-S-REGOUT)") (class "Default")
      (node (ref "C1-1S") (pin "1") (pinfunction "1_1") (pintype "passive"))
      (node (ref "U1-S") (pin "10") (pinfunction "REGOUT_10") (pintype "bidirectional"))
    )
    (net (code "64") (name "Net-(U2-S-VOUT)") (class "Default")
      (node (ref "R3-2S") (pin "1") (pinfunction "1_1") (pintype "passive"))
      (node (ref "U2-S") (pin "5") (pinfunction "VOUT_5") (pintype "bidirectional"))
    )
    (net (code "65") (name "SENSOR-ERROR") (class "Default")
      (node (ref "J3-CS") (pin "2") (pinfunction "2_2") (pintype "passive"))
      (node (ref "R2A-S") (pin "1") (pinfunction "1_1") (pintype "passive"))
      (node (ref "R2B-S") (pin "1") (pinfunction "1_1") (pintype "passive"))
      (node (ref "R2C-S") (pin "1") (pinfunction "1_1") (pintype "passive"))
      (node (ref "R2D-S") (pin "1") (pinfunction "1_1") (pintype "passive"))
    )
    (net (code "66") (name "SENSOR-NOMINAL") (class "Default")
      (node (ref "J3-CS") (pin "1") (pinfunction "1_1") (pintype "passive"))
      (node (ref "R1A-S") (pin "1") (pinfunction "1_1") (pintype "passive"))
      (node (ref "R1B-S") (pin "1") (pinfunction "1_1") (pintype "passive"))
      (node (ref "R1C-S") (pin "1") (pinfunction "1_1") (pintype "passive"))
      (node (ref "R1D-S") (pin "1") (pinfunction "1_1") (pintype "passive"))
    )
    (net (code "67") (name "U1S-CHECK") (class "Default")
      (node (ref "J3-CS") (pin "3") (pinfunction "3_3") (pintype "passive"))
      (node (ref "R2A-1S") (pin "1") (pinfunction "1_1") (pintype "passive"))
      (node (ref "R2B-1S") (pin "1") (pinfunction "1_1") (pintype "passive"))
    )
    (net (code "68") (name "U2S-CHECK") (class "Default")
      (node (ref "D2A-2S") (pin "A") (pinfunction "A_A") (pintype "passive"))
      (node (ref "J3-CS") (pin "4") (pinfunction "4_4") (pintype "passive"))
      (node (ref "R2B-2S") (pin "1") (pinfunction "1_1") (pintype "passive"))
    )
    (net (code "69") (name "U2S-ST") (class "Default")
      (node (ref "J3-CS") (pin "7") (pinfunction "7_7") (pintype "passive"))
      (node (ref "U2-S") (pin "4") (pinfunction "ST_4") (pintype "bidirectional"))
    )
    (net (code "71") (name "U3S-CHECK") (class "Default")
      (node (ref "J3-CS") (pin "5") (pinfunction "5_5") (pintype "passive"))
      (node (ref "R2A-3S") (pin "1") (pinfunction "1_1") (pintype "passive"))
      (node (ref "R2B-3S") (pin "1") (pinfunction "1_1") (pintype "passive"))
    )
    (net (code "73") (name "U4S-CHECK") (class "Default")
      (node (ref "D2A-4S") (pin "A") (pinfunction "A_A") (pintype "passive"))
      (node (ref "J3-CS") (pin "6") (pinfunction "6_6") (pintype "passive"))
      (node (ref "R2B-4S") (pin "1") (pinfunction "1_1") (pintype "passive"))
    )
    (net (code "74") (name "US2-STATUS") (class "Default")
      (node (ref "J3-CS") (pin "8") (pinfunction "8_8") (pintype "passive"))
      (node (ref "U2-S") (pin "6") (pinfunction "STATUS_6") (pintype "bidirectional"))
    )
    (net (code "75") (name "unconnected-(U1-S-AUX_CL-Pad7)") (class "Default")
      (node (ref "U1-S") (pin "7") (pinfunction "AUX_CL_7") (pintype "bidirectional"))
    )
    (net (code "76") (name "unconnected-(U1-S-AUX_DA-Pad21)") (class "Default")
      (node (ref "U1-S") (pin "21") (pinfunction "AUX_DA_21") (pintype "bidirectional"))
    )
    (net (code "77") (name "unconnected-(U1-S-FSYNC-Pad11)") (class "Default")
      (node (ref "U1-S") (pin "11") (pinfunction "FSYNC_11") (pintype "bidirectional"))
    )
    (net (code "78") (name "unconnected-(U1-S-INT1-Pad12)") (class "Default")
      (node (ref "U1-S") (pin "12") (pinfunction "INT1_12") (pintype "bidirectional"))
    )
    (net (code "79") (name "unconnected-(U1-S-NC.1-Pad1)") (class "Default")
      (node (ref "U1-S") (pin "1") (pinfunction "NC.1_1") (pintype "bidirectional"))
    )
    (net (code "80") (name "unconnected-(U1-S-NC.2-Pad2)") (class "Default")
      (node (ref "U1-S") (pin "2") (pinfunction "NC.2_2") (pintype "bidirectional"))
    )
    (net (code "81") (name "unconnected-(U1-S-NC.3-Pad3)") (class "Default")
      (node (ref "U1-S") (pin "3") (pinfunction "NC.3_3") (pintype "bidirectional"))
    )
    (net (code "82") (name "unconnected-(U1-S-NC.4-Pad4)") (class "Default")
      (node (ref "U1-S") (pin "4") (pinfunction "NC.4_4") (pintype "bidirectional"))
    )
    (net (code "83") (name "unconnected-(U1-S-NC.5-Pad5)") (class "Default")
      (node (ref "U1-S") (pin "5") (pinfunction "NC.5_5") (pintype "bidirectional"))
    )
    (net (code "84") (name "unconnected-(U1-S-NC.6-Pad6)") (class "Default")
      (node (ref "U1-S") (pin "6") (pinfunction "NC.6_6") (pintype "bidirectional"))
    )
    (net (code "85") (name "unconnected-(U1-S-NC.14-Pad14)") (class "Default")
      (node (ref "U1-S") (pin "14") (pinfunction "NC.14_14") (pintype "bidirectional"))
    )
    (net (code "86") (name "unconnected-(U1-S-NC.15-Pad15)") (class "Default")
      (node (ref "U1-S") (pin "15") (pinfunction "NC.15_15") (pintype "bidirectional"))
    )
    (net (code "87") (name "unconnected-(U1-S-NC.16-Pad16)") (class "Default")
      (node (ref "U1-S") (pin "16") (pinfunction "NC.16_16") (pintype "bidirectional"))
    )
    (net (code "88") (name "unconnected-(U1-S-NC.17-Pad17)") (class "Default")
      (node (ref "U1-S") (pin "17") (pinfunction "NC.17_17") (pintype "bidirectional"))
    )
    (net (code "89") (name "unconnected-(U1-S-RESV.NC-Pad19)") (class "Default")
      (node (ref "U1-S") (pin "19") (pinfunction "RESV.NC_19") (pintype "bidirectional"))
    )
    (net (code "90") (name "unconnected-(U4-S-1PPS-Pad13)") (class "Default")
      (node (ref "U4-S") (pin "13") (pinfunction "1PPS_13") (pintype "bidirectional"))
    )
    (net (code "91") (name "unconnected-(U4-S-NREST-Pad2)") (class "Default")
      (node (ref "U4-S") (pin "2") (pinfunction "NREST_2") (pintype "bidirectional"))
    )
    (net (code "92") (name "unconnected-(U4-S-RTCM-Pad14)") (class "Default")
      (node (ref "U4-S") (pin "14") (pinfunction "RTCM_14") (pintype "bidirectional"))
    )
    (net (code "93") (name "unconnected-(U4-S-VBACKUP-Pad4)") (class "Default")
      (node (ref "U4-S") (pin "4") (pinfunction "VBACKUP_4") (pintype "bidirectional"))
    )
  )
)
